# BMSIOConnector.net
KiCad netlist of a schematic drawn in Altium Designer
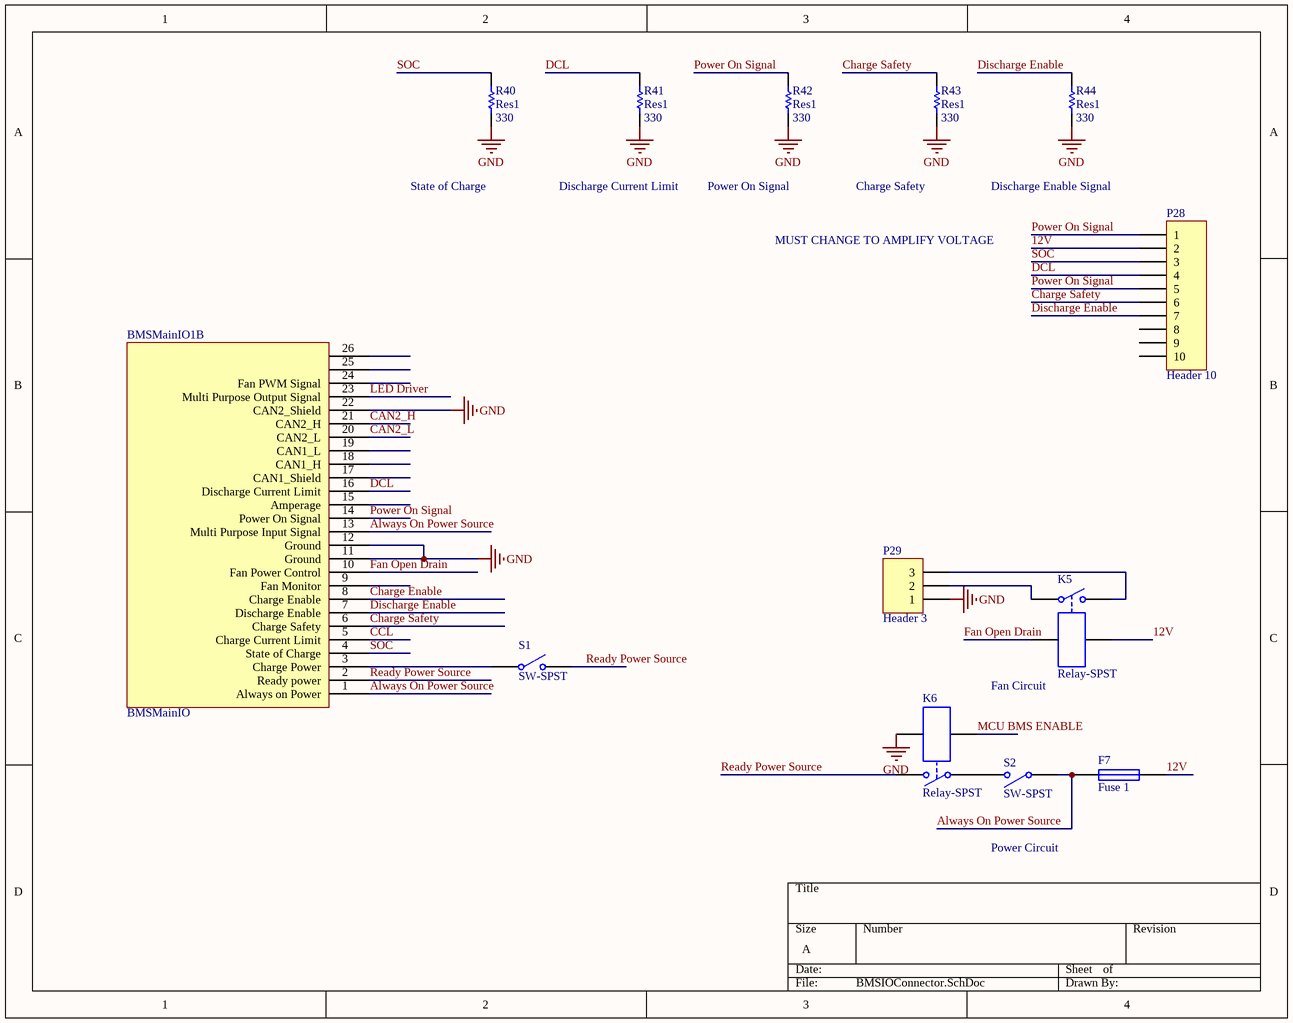
[diagram p0: BMSIOConnector.SchDoc]

(export (version "E")
  (design (tool "Eeschema 10.0.6"))
  (components
    (comp (ref "BMSMainIO1") (value "BMSMainIO") (libsource (lib "Pod3") (part "BMSMainIO")))
    (comp (ref "F7")
      (value "Fuse 1")
      (footprint "PIN-W2/E2.8")
      (description "Fuse")
      (fields (field (name "PUBLISHER") "Altium Limited"))
      (libsource (lib "Miscellaneous Devices") (part "Fuse 1"))
    )
    (comp (ref "K5")
      (value "Relay-SPST")
      (footprint "MODULE4")
      (description "Single-Pole Single-Throw Relay")
      (fields (field (name "PUBLISHER") "Altium Limited"))
      (libsource (lib "Miscellaneous Devices") (part "Relay-SPST"))
    )
    (comp (ref "K6")
      (value "Relay-SPST")
      (footprint "MODULE4")
      (description "Single-Pole Single-Throw Relay")
      (fields (field (name "PUBLISHER") "Altium Limited"))
      (libsource (lib "Miscellaneous Devices") (part "Relay-SPST"))
    )
    (comp (ref "P28")
      (value "Header 10")
      (footprint "HDR1X10")
      (description "Header, 10-Pin")
      (fields (field (name "PUBLISHER") "Altium Limited"))
      (libsource (lib "Miscellaneous Connectors") (part "Header 10"))
    )
    (comp (ref "P29")
      (value "Header 3")
      (footprint "HDR1X3")
      (description "Header, 3-Pin")
      (fields (field (name "PUBLISHER") "Altium Limited"))
      (libsource (lib "Miscellaneous Connectors") (part "Header 3"))
    )
    (comp (ref "R40")
      (value "Res1")
      (footprint "AXIAL-0.3")
      (description "Resistor")
      (fields (field (name "ALTIUM_VALUE") "330") (field (name "PUBLISHER") "Altium Limited"))
      (libsource (lib "Miscellaneous Devices") (part "Res1"))
    )
    (comp (ref "R41")
      (value "Res1")
      (footprint "AXIAL-0.3")
      (description "Resistor")
      (fields (field (name "ALTIUM_VALUE") "330") (field (name "PUBLISHER") "Altium Limited"))
      (libsource (lib "Miscellaneous Devices") (part "Res1"))
    )
    (comp (ref "R42")
      (value "Res1")
      (footprint "AXIAL-0.3")
      (description "Resistor")
      (fields (field (name "ALTIUM_VALUE") "330") (field (name "PUBLISHER") "Altium Limited"))
      (libsource (lib "Miscellaneous Devices") (part "Res1"))
    )
    (comp (ref "R43")
      (value "Res1")
      (footprint "AXIAL-0.3")
      (description "Resistor")
      (fields (field (name "ALTIUM_VALUE") "330") (field (name "PUBLISHER") "Altium Limited"))
      (libsource (lib "Miscellaneous Devices") (part "Res1"))
    )
    (comp (ref "R44")
      (value "Res1")
      (footprint "AXIAL-0.3")
      (description "Resistor")
      (fields (field (name "ALTIUM_VALUE") "330") (field (name "PUBLISHER") "Altium Limited"))
      (libsource (lib "Miscellaneous Devices") (part "Res1"))
    )
    (comp (ref "S1")
      (value "SW-SPST")
      (footprint "SPST-2")
      (description "Single-Pole, Single-Throw Switch")
      (fields (field (name "PUBLISHER") "Altium Limited"))
      (libsource (lib "Miscellaneous Devices") (part "SW-SPST"))
    )
    (comp (ref "S2")
      (value "SW-SPST")
      (footprint "SPST-2")
      (description "Single-Pole, Single-Throw Switch")
      (fields (field (name "PUBLISHER") "Altium Limited"))
      (libsource (lib "Miscellaneous Devices") (part "SW-SPST"))
    )
  )
  (nets
    (net (code "1") (name "/12V") (class "Default")
      (node (ref "F7") (pin "2") (pinfunction "2_2") (pintype "passive"))
      (node (ref "K5") (pin "4") (pinfunction "4_4") (pintype "passive"))
      (node (ref "P28") (pin "2") (pinfunction "2_2") (pintype "passive"))
    )
    (net (code "2") (name "/Always On Power Source") (class "Default")
      (node (ref "BMSMainIO1") (pin "1") (pinfunction "Always_on_Power_1") (pintype "passive"))
      (node (ref "BMSMainIO1") (pin "13") (pinfunction "Multi_Purpose_Input_Signal_13") (pintype "passive"))
      (node (ref "F7") (pin "1") (pinfunction "1_1") (pintype "passive"))
      (node (ref "S2") (pin "1") (pinfunction "COMMON_1") (pintype "passive"))
    )
    (net (code "3") (name "/CAN2_H") (class "Default")
      (node (ref "BMSMainIO1") (pin "21") (pinfunction "CAN2_H_21") (pintype "passive"))
    )
    (net (code "4") (name "/CAN2_L") (class "Default")
      (node (ref "BMSMainIO1") (pin "20") (pinfunction "CAN2_L_20") (pintype "passive"))
    )
    (net (code "5") (name "/CCL") (class "Default")
      (node (ref "BMSMainIO1") (pin "5") (pinfunction "Charge_Current_Limit_5") (pintype "passive"))
    )
    (net (code "6") (name "/Charge Enable") (class "Default")
      (node (ref "BMSMainIO1") (pin "8") (pinfunction "Charge_Enable_8") (pintype "passive"))
    )
    (net (code "7") (name "/Charge Safety") (class "Default")
      (node (ref "BMSMainIO1") (pin "6") (pinfunction "Charge_Safety_6") (pintype "passive"))
      (node (ref "P28") (pin "6") (pinfunction "6_6") (pintype "passive"))
      (node (ref "R43") (pin "1") (pinfunction "1_1") (pintype "passive"))
    )
    (net (code "8") (name "/DCL") (class "Default")
      (node (ref "BMSMainIO1") (pin "16") (pinfunction "Discharge_Current_Limit_16") (pintype "passive"))
      (node (ref "P28") (pin "4") (pinfunction "4_4") (pintype "passive"))
      (node (ref "R41") (pin "1") (pinfunction "1_1") (pintype "passive"))
    )
    (net (code "9") (name "/Discharge Enable") (class "Default")
      (node (ref "BMSMainIO1") (pin "7") (pinfunction "Discharge_Enable_7") (pintype "passive"))
      (node (ref "P28") (pin "7") (pinfunction "7_7") (pintype "passive"))
      (node (ref "R44") (pin "1") (pinfunction "1_1") (pintype "passive"))
    )
    (net (code "10") (name "/Fan Open Drain") (class "Default")
      (node (ref "BMSMainIO1") (pin "10") (pinfunction "Fan_Power_Control_10") (pintype "passive"))
      (node (ref "K5") (pin "3") (pinfunction "3_3") (pintype "passive"))
    )
    (net (code "11") (name "/LED Driver") (class "Default")
      (node (ref "BMSMainIO1") (pin "23") (pinfunction "Multi_Purpose_Output_Signal_23") (pintype "passive"))
    )
    (net (code "12") (name "/MCU BMS ENABLE") (class "Default")
      (node (ref "K6") (pin "3") (pinfunction "3_3") (pintype "passive"))
    )
    (net (code "13") (name "/Power On Signal") (class "Default")
      (node (ref "BMSMainIO1") (pin "14") (pinfunction "Power_On_Signal_14") (pintype "passive"))
      (node (ref "P28") (pin "1") (pinfunction "1_1") (pintype "passive"))
      (node (ref "P28") (pin "5") (pinfunction "5_5") (pintype "passive"))
      (node (ref "R42") (pin "1") (pinfunction "1_1") (pintype "passive"))
    )
    (net (code "14") (name "/Ready Power Source") (class "Default")
      (node (ref "BMSMainIO1") (pin "2") (pinfunction "Ready_power_2") (pintype "passive"))
      (node (ref "K6") (pin "2") (pinfunction "2_2") (pintype "passive"))
      (node (ref "S1") (pin "2") (pinfunction "NO_2") (pintype "passive"))
    )
    (net (code "15") (name "/SOC") (class "Default")
      (node (ref "BMSMainIO1") (pin "4") (pinfunction "State_of_Charge_4") (pintype "passive"))
      (node (ref "P28") (pin "3") (pinfunction "3_3") (pintype "passive"))
      (node (ref "R40") (pin "1") (pinfunction "1_1") (pintype "passive"))
    )
    (net (code "16") (name "GND") (class "Default")
      (node (ref "BMSMainIO1") (pin "11") (pinfunction "Ground_11") (pintype "passive"))
      (node (ref "BMSMainIO1") (pin "12") (pinfunction "Ground_12") (pintype "passive"))
      (node (ref "BMSMainIO1") (pin "22") (pinfunction "CAN2_Shield_22") (pintype "passive"))
      (node (ref "K6") (pin "4") (pinfunction "4_4") (pintype "passive"))
      (node (ref "P29") (pin "1") (pinfunction "1_1") (pintype "passive"))
      (node (ref "R40") (pin "2") (pinfunction "2_2") (pintype "passive"))
      (node (ref "R41") (pin "2") (pinfunction "2_2") (pintype "passive"))
      (node (ref "R42") (pin "2") (pinfunction "2_2") (pintype "passive"))
      (node (ref "R43") (pin "2") (pinfunction "2_2") (pintype "passive"))
      (node (ref "R44") (pin "2") (pinfunction "2_2") (pintype "passive"))
    )
    (net (code "17") (name "Net-(BMSMainIO1B-Charge_Power)") (class "Default")
      (node (ref "BMSMainIO1") (pin "3") (pinfunction "Charge_Power_3") (pintype "passive"))
      (node (ref "S1") (pin "1") (pinfunction "COMMON_1") (pintype "passive"))
    )
    (net (code "18") (name "Net-(K5-Pad1)") (class "Default")
      (node (ref "K5") (pin "1") (pinfunction "1_1") (pintype "passive"))
      (node (ref "P29") (pin "2") (pinfunction "2_2") (pintype "passive"))
    )
    (net (code "19") (name "Net-(K5-Pad2)") (class "Default")
      (node (ref "K5") (pin "2") (pinfunction "2_2") (pintype "passive"))
      (node (ref "P29") (pin "3") (pinfunction "3_3") (pintype "passive"))
    )
    (net (code "20") (name "Net-(S2-NO)") (class "Default")
      (node (ref "K6") (pin "1") (pinfunction "1_1") (pintype "passive"))
      (node (ref "S2") (pin "2") (pinfunction "NO_2") (pintype "passive"))
    )
    (net (code "21") (name "unconnected-(BMSMainIO1-Pad25)") (class "Default")
      (node (ref "BMSMainIO1") (pin "25") (pintype "passive"))
    )
    (net (code "22") (name "unconnected-(BMSMainIO1-Pad26)") (class "Default")
      (node (ref "BMSMainIO1") (pin "26") (pintype "passive"))
    )
    (net (code "23") (name "unconnected-(BMSMainIO1B-Amperage-Pad15)") (class "Default")
      (node (ref "BMSMainIO1") (pin "15") (pinfunction "Amperage_15") (pintype "passive"))
    )
    (net (code "24") (name "unconnected-(BMSMainIO1B-CAN1_H-Pad18)") (class "Default")
      (node (ref "BMSMainIO1") (pin "18") (pinfunction "CAN1_H_18") (pintype "passive"))
    )
    (net (code "25") (name "unconnected-(BMSMainIO1B-CAN1_L-Pad19)") (class "Default")
      (node (ref "BMSMainIO1") (pin "19") (pinfunction "CAN1_L_19") (pintype "passive"))
    )
    (net (code "26") (name "unconnected-(BMSMainIO1B-CAN1_Shield-Pad17)") (class "Default")
      (node (ref "BMSMainIO1") (pin "17") (pinfunction "CAN1_Shield_17") (pintype "passive"))
    )
    (net (code "27") (name "unconnected-(BMSMainIO1B-Fan_Monitor-Pad9)") (class "Default")
      (node (ref "BMSMainIO1") (pin "9") (pinfunction "Fan_Monitor_9") (pintype "passive"))
    )
    (net (code "28") (name "unconnected-(BMSMainIO1B-Fan_PWM_Signal-Pad24)") (class "Default")
      (node (ref "BMSMainIO1") (pin "24") (pinfunction "Fan_PWM_Signal_24") (pintype "passive"))
    )
    (net (code "29") (name "unconnected-(P28-Pad8)") (class "Default")
      (node (ref "P28") (pin "8") (pinfunction "8_8") (pintype "passive"))
    )
    (net (code "30") (name "unconnected-(P28-Pad9)") (class "Default")
      (node (ref "P28") (pin "9") (pinfunction "9_9") (pintype "passive"))
    )
    (net (code "31") (name "unconnected-(P28-Pad10)") (class "Default")
      (node (ref "P28") (pin "10") (pinfunction "10_10") (pintype "passive"))
    )
  )
)
